# cpc_rct_mouse.net
KiCad netlist of a schematic drawn in EAGLE
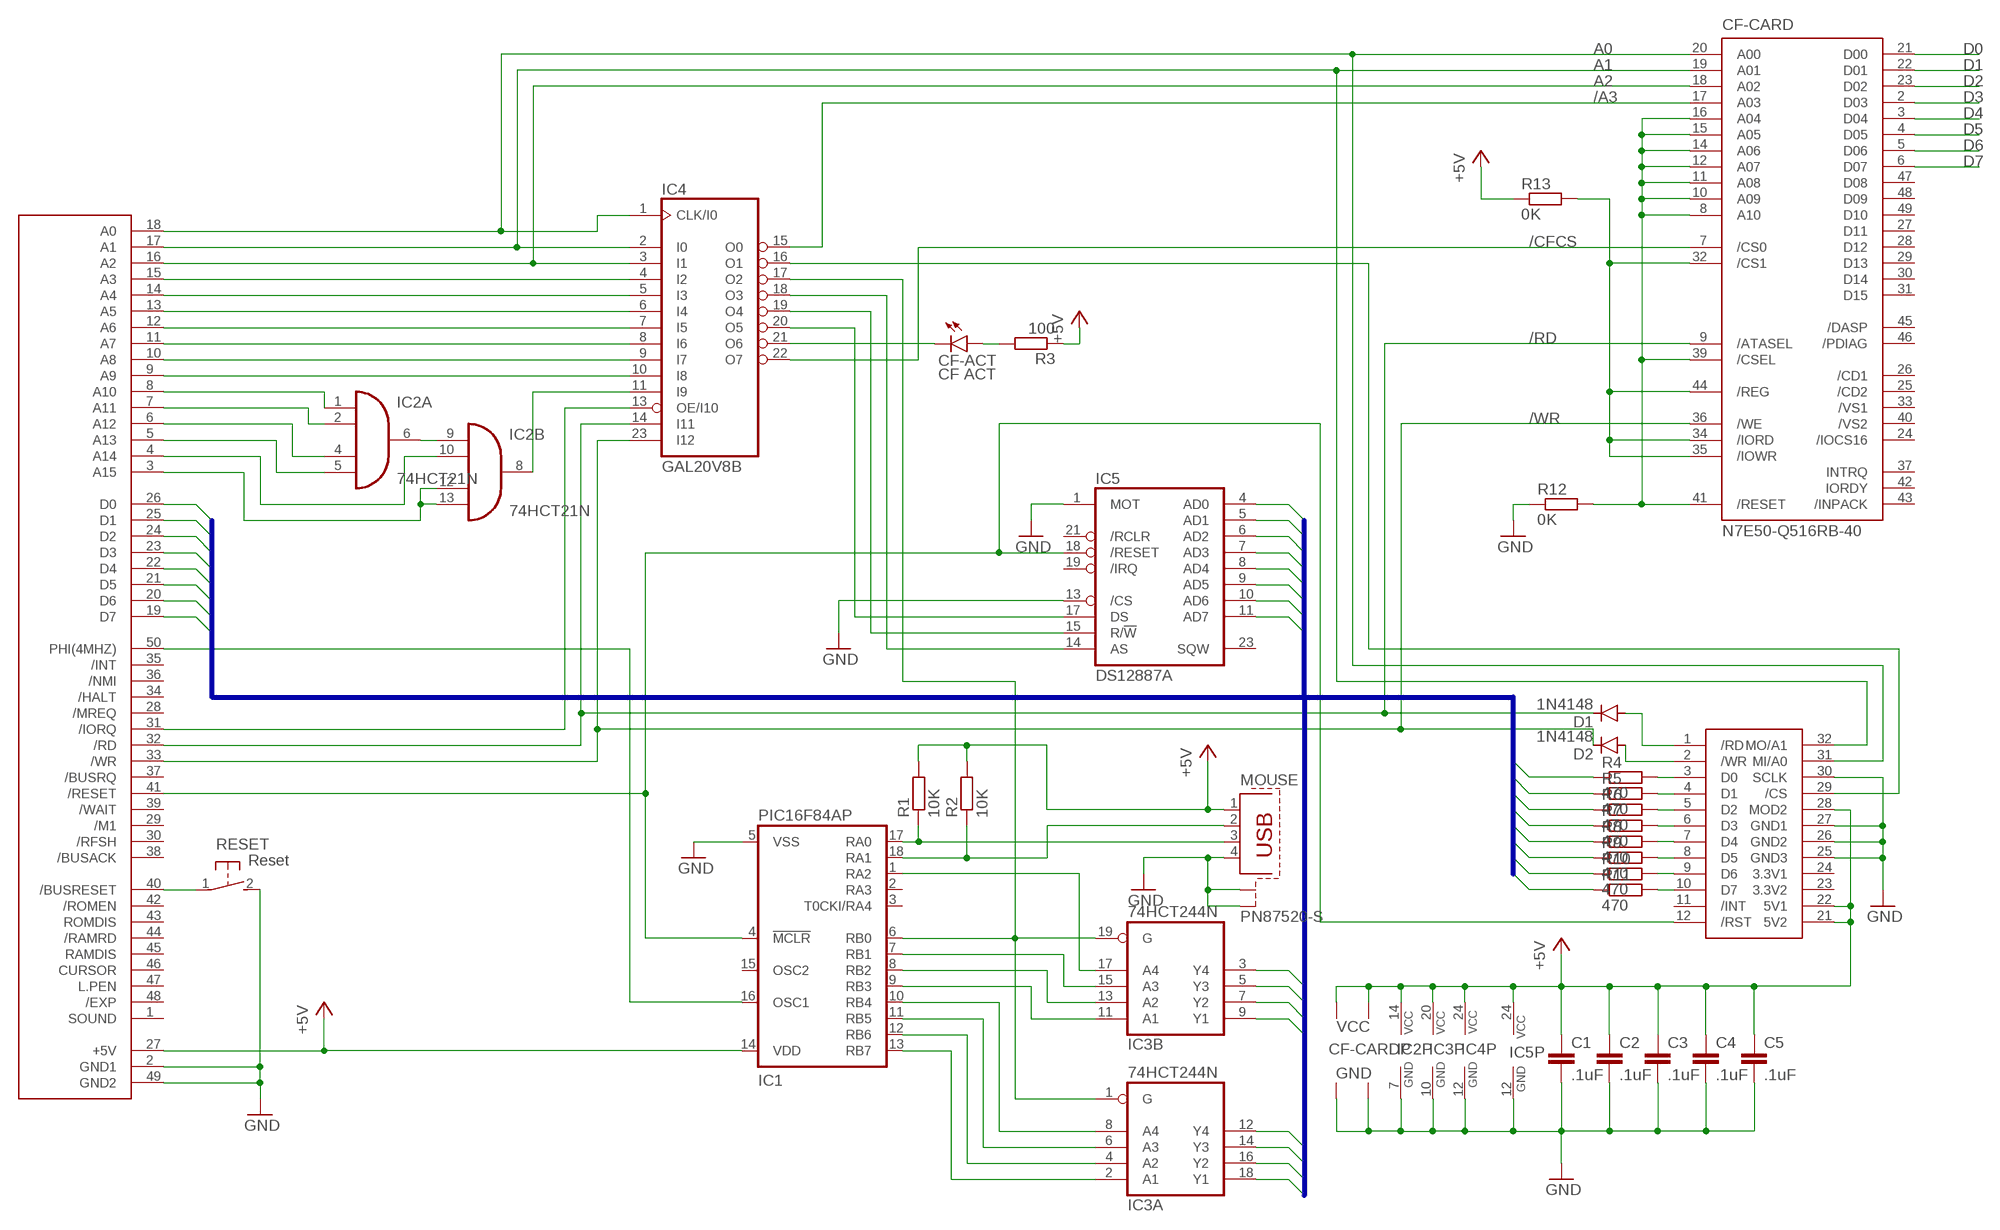
[diagram p0: schematic, sheet 1]

(export (version "E")
  (design (tool "Eeschema 10.0.6"))
  (components
    (comp (ref "C1")
      (value ".1uF")
      (footprint "eagle-import:C025-025X050")
      (libsource (lib "eagle-import") (part "C-EU025-025X050"))
    )
    (comp (ref "C2")
      (value ".1uF")
      (footprint "eagle-import:C025-025X050")
      (libsource (lib "eagle-import") (part "C-EU025-025X050"))
    )
    (comp (ref "C3")
      (value ".1uF")
      (footprint "eagle-import:C025-025X050")
      (libsource (lib "eagle-import") (part "C-EU025-025X050"))
    )
    (comp (ref "C4")
      (value ".1uF")
      (footprint "eagle-import:C025-025X050")
      (libsource (lib "eagle-import") (part "C-EU025-025X050"))
    )
    (comp (ref "C5")
      (value ".1uF")
      (footprint "eagle-import:C025-025X050")
      (libsource (lib "eagle-import") (part "C-EU025-025X050"))
    )
    (comp (ref "CF-ACT")
      (value "CF ACT")
      (footprint "eagle-import:LED3MM")
      (libsource (lib "eagle-import") (part "LED3MM"))
    )
    (comp (ref "CF-CARD")
      (value "N7E50-Q516RB-40")
      (footprint "eagle-import:3M-N7E50")
      (libsource (lib "eagle-import") (part "CF-CARD-HEADERHYBRID-1"))
    )
    (comp (ref "CON1")
      (value "CPCBUS")
      (footprint "eagle-import:2X25")
      (libsource (lib "eagle-import") (part "AMSTRAD_CPC_BUSP"))
    )
    (comp (ref "D1")
      (value "1N4148")
      (footprint "eagle-import:DO35-7")
      (libsource (lib "eagle-import") (part "1N4148DO35-7"))
    )
    (comp (ref "D2")
      (value "1N4148")
      (footprint "eagle-import:DO35-7")
      (libsource (lib "eagle-import") (part "1N4148DO35-7"))
    )
    (comp (ref "IC1")
      (value "PIC16F84AP")
      (footprint "eagle-import:DIL18")
      (fields (field (name "MF") "MICROCHIP") (field (name "MPN") "PIC16F84A-04I/P"))
      (libsource (lib "eagle-import") (part "PIC16F8P4A"))
    )
    (comp (ref "IC2")
      (value "74HCT21N")
      (footprint "eagle-import:DIL14")
      (libsource (lib "eagle-import") (part "7421NHC"))
    )
    (comp (ref "IC3")
      (value "74HCT244N")
      (footprint "eagle-import:DIL20")
      (libsource (lib "eagle-import") (part "74244NHCT"))
    )
    (comp (ref "IC4")
      (value "GAL20V8B")
      (footprint "eagle-import:DIL24-3")
      (fields (field (name "MF") "FARNELL") (field (name "MPN") "GAL20V8B-25QP"))
      (libsource (lib "eagle-import") (part "20V8"))
    )
    (comp (ref "IC5")
      (value "DS12887A")
      (footprint "eagle-import:DIL24")
      (libsource (lib "eagle-import") (part "DS12887"))
    )
    (comp (ref "MOUSE")
      (value "PN87520-S")
      (footprint "eagle-import:PN87520-S")
      (libsource (lib "eagle-import") (part "PN87520-S"))
    )
    (comp (ref "R1")
      (value "10K")
      (footprint "eagle-import:0204_7")
      (libsource (lib "eagle-import") (part "R-EU_0204/7"))
    )
    (comp (ref "R2")
      (value "10K")
      (footprint "eagle-import:0204_7")
      (libsource (lib "eagle-import") (part "R-EU_0204/7"))
    )
    (comp (ref "R3")
      (value "100")
      (footprint "eagle-import:0204_7")
      (libsource (lib "eagle-import") (part "R-EU_0204/7"))
    )
    (comp (ref "R4")
      (value "470")
      (footprint "eagle-import:0204_7")
      (libsource (lib "eagle-import") (part "R-EU_0204/7"))
    )
    (comp (ref "R5")
      (value "470")
      (footprint "eagle-import:0204_7")
      (libsource (lib "eagle-import") (part "R-EU_0204/7"))
    )
    (comp (ref "R6")
      (value "470")
      (footprint "eagle-import:0204_7")
      (libsource (lib "eagle-import") (part "R-EU_0204/7"))
    )
    (comp (ref "R7")
      (value "470")
      (footprint "eagle-import:0204_7")
      (libsource (lib "eagle-import") (part "R-EU_0204/7"))
    )
    (comp (ref "R8")
      (value "470")
      (footprint "eagle-import:0204_7")
      (libsource (lib "eagle-import") (part "R-EU_0204/7"))
    )
    (comp (ref "R9")
      (value "470")
      (footprint "eagle-import:0204_7")
      (libsource (lib "eagle-import") (part "R-EU_0204/7"))
    )
    (comp (ref "R10")
      (value "470")
      (footprint "eagle-import:0204_7")
      (libsource (lib "eagle-import") (part "R-EU_0204/7"))
    )
    (comp (ref "R11")
      (value "470")
      (footprint "eagle-import:0204_7")
      (libsource (lib "eagle-import") (part "R-EU_0204/7"))
    )
    (comp (ref "R12")
      (value "0K")
      (footprint "eagle-import:0204_7")
      (libsource (lib "eagle-import") (part "R-EU_0204/7"))
    )
    (comp (ref "R13")
      (value "0K")
      (footprint "eagle-import:0204_7")
      (libsource (lib "eagle-import") (part "R-EU_0204/7"))
    )
    (comp (ref "RESET")
      (value "Reset")
      (footprint "eagle-import:B3F-31XX")
      (fields (field (name "MPN") "B3F-3100"))
      (libsource (lib "eagle-import") (part "31-XX"))
    )
    (comp (ref "W5100S-MODULE")
      (value "W5100S-NETWORK-MODULE")
      (footprint "eagle-import:W5100S-NETWORK-MODULE")
      (libsource (lib "eagle-import") (part "W5100S-NETWORK-MODULE"))
    )
  )
  (nets
    (net (code "1") (name "+5V") (class "Default")
      (node (ref "C1") (pin "1") (pinfunction "1_1") (pintype "passive"))
      (node (ref "C2") (pin "1") (pinfunction "1_1") (pintype "passive"))
      (node (ref "C3") (pin "1") (pinfunction "1_1") (pintype "passive"))
      (node (ref "C4") (pin "1") (pinfunction "1_1") (pintype "passive"))
      (node (ref "C5") (pin "1") (pinfunction "1_1") (pintype "passive"))
      (node (ref "CF-CARD") (pin "13") (pinfunction "VCC2_13") (pintype "power_in"))
      (node (ref "CF-CARD") (pin "38") (pinfunction "VCC1_38") (pintype "power_in"))
      (node (ref "CON1") (pin "27") (pinfunction "+5V_27") (pintype "bidirectional"))
      (node (ref "IC1") (pin "14") (pinfunction "VDD_14") (pintype "power_in"))
      (node (ref "IC2") (pin "14") (pinfunction "VCC_14") (pintype "power_in"))
      (node (ref "IC3") (pin "20") (pinfunction "VCC_20") (pintype "power_in"))
      (node (ref "IC4") (pin "24") (pinfunction "VCC_24") (pintype "power_in"))
      (node (ref "IC5") (pin "24") (pinfunction "VCC_24") (pintype "power_in"))
      (node (ref "MOUSE") (pin "1") (pinfunction "1_1") (pintype "passive"))
      (node (ref "R1") (pin "2") (pinfunction "2_2") (pintype "passive"))
      (node (ref "R13") (pin "1") (pinfunction "1_1") (pintype "passive"))
      (node (ref "R2") (pin "2") (pinfunction "2_2") (pintype "passive"))
      (node (ref "R3") (pin "1") (pinfunction "1_1") (pintype "passive"))
      (node (ref "W5100S-MODULE") (pin "21") (pinfunction "5V2_21") (pintype "power_in"))
      (node (ref "W5100S-MODULE") (pin "22") (pinfunction "5V1_22") (pintype "power_in"))
      (node (ref "W5100S-MODULE") (pin "28") (pinfunction "MOD2_28") (pintype "passive"))
    )
    (net (code "2") (name "/3.3V1") (class "Default")
      (node (ref "W5100S-MODULE") (pin "24") (pinfunction "3.3V1_24") (pintype "power_in"))
    )
    (net (code "3") (name "/3.3V2") (class "Default")
      (node (ref "W5100S-MODULE") (pin "23") (pinfunction "3.3V2_23") (pintype "power_in"))
    )
    (net (code "4") (name "/A0") (class "Default")
      (node (ref "CF-CARD") (pin "20") (pinfunction "A00_20") (pintype "input"))
      (node (ref "CON1") (pin "18") (pinfunction "A0_18") (pintype "bidirectional"))
      (node (ref "IC4") (pin "1") (pinfunction "CLK/I0_1") (pintype "input"))
      (node (ref "W5100S-MODULE") (pin "31") (pinfunction "MI/A0_31") (pintype "input"))
    )
    (net (code "5") (name "/A1") (class "Default")
      (node (ref "CF-CARD") (pin "19") (pinfunction "A01_19") (pintype "input"))
      (node (ref "CON1") (pin "17") (pinfunction "A1_17") (pintype "bidirectional"))
      (node (ref "IC4") (pin "2") (pinfunction "I0_2") (pintype "input"))
      (node (ref "W5100S-MODULE") (pin "32") (pinfunction "MO/A1_32") (pintype "bidirectional"))
    )
    (net (code "6") (name "/A2") (class "Default")
      (node (ref "CF-CARD") (pin "18") (pinfunction "A02_18") (pintype "input"))
      (node (ref "CON1") (pin "16") (pinfunction "A2_16") (pintype "bidirectional"))
      (node (ref "IC4") (pin "3") (pinfunction "I1_3") (pintype "input"))
    )
    (net (code "7") (name "/D0") (class "Default")
      (node (ref "CF-CARD") (pin "21") (pinfunction "D00_21") (pintype "bidirectional"))
      (node (ref "CON1") (pin "26") (pinfunction "D0_26") (pintype "bidirectional"))
      (node (ref "IC3") (pin "3") (pinfunction "Y4_3") (pintype "tri_state"))
      (node (ref "IC5") (pin "4") (pinfunction "AD0_4") (pintype "bidirectional"))
      (node (ref "R4") (pin "1") (pinfunction "1_1") (pintype "passive"))
    )
    (net (code "8") (name "/D1") (class "Default")
      (node (ref "CF-CARD") (pin "22") (pinfunction "D01_22") (pintype "bidirectional"))
      (node (ref "CON1") (pin "25") (pinfunction "D1_25") (pintype "bidirectional"))
      (node (ref "IC3") (pin "5") (pinfunction "Y3_5") (pintype "tri_state"))
      (node (ref "IC5") (pin "5") (pinfunction "AD1_5") (pintype "bidirectional"))
      (node (ref "R5") (pin "1") (pinfunction "1_1") (pintype "passive"))
    )
    (net (code "9") (name "/D2") (class "Default")
      (node (ref "CF-CARD") (pin "23") (pinfunction "D02_23") (pintype "bidirectional"))
      (node (ref "CON1") (pin "24") (pinfunction "D2_24") (pintype "bidirectional"))
      (node (ref "IC3") (pin "7") (pinfunction "Y2_7") (pintype "tri_state"))
      (node (ref "IC5") (pin "6") (pinfunction "AD2_6") (pintype "bidirectional"))
      (node (ref "R6") (pin "1") (pinfunction "1_1") (pintype "passive"))
    )
    (net (code "10") (name "/D3") (class "Default")
      (node (ref "CF-CARD") (pin "2") (pinfunction "D03_2") (pintype "bidirectional"))
      (node (ref "CON1") (pin "23") (pinfunction "D3_23") (pintype "bidirectional"))
      (node (ref "IC3") (pin "9") (pinfunction "Y1_9") (pintype "tri_state"))
      (node (ref "IC5") (pin "7") (pinfunction "AD3_7") (pintype "bidirectional"))
      (node (ref "R7") (pin "1") (pinfunction "1_1") (pintype "passive"))
    )
    (net (code "11") (name "/D4") (class "Default")
      (node (ref "CF-CARD") (pin "3") (pinfunction "D04_3") (pintype "bidirectional"))
      (node (ref "CON1") (pin "22") (pinfunction "D4_22") (pintype "bidirectional"))
      (node (ref "IC3") (pin "12") (pinfunction "Y4_12") (pintype "tri_state"))
      (node (ref "IC5") (pin "8") (pinfunction "AD4_8") (pintype "bidirectional"))
      (node (ref "R8") (pin "1") (pinfunction "1_1") (pintype "passive"))
    )
    (net (code "12") (name "/D5") (class "Default")
      (node (ref "CF-CARD") (pin "4") (pinfunction "D05_4") (pintype "bidirectional"))
      (node (ref "CON1") (pin "21") (pinfunction "D5_21") (pintype "bidirectional"))
      (node (ref "IC3") (pin "14") (pinfunction "Y3_14") (pintype "tri_state"))
      (node (ref "IC5") (pin "9") (pinfunction "AD5_9") (pintype "bidirectional"))
      (node (ref "R9") (pin "1") (pinfunction "1_1") (pintype "passive"))
    )
    (net (code "13") (name "/D6") (class "Default")
      (node (ref "CF-CARD") (pin "5") (pinfunction "D06_5") (pintype "bidirectional"))
      (node (ref "CON1") (pin "20") (pinfunction "D6_20") (pintype "bidirectional"))
      (node (ref "IC3") (pin "16") (pinfunction "Y2_16") (pintype "tri_state"))
      (node (ref "IC5") (pin "10") (pinfunction "AD6_10") (pintype "bidirectional"))
      (node (ref "R10") (pin "1") (pinfunction "1_1") (pintype "passive"))
    )
    (net (code "14") (name "/D7") (class "Default")
      (node (ref "CF-CARD") (pin "6") (pinfunction "D07_6") (pintype "bidirectional"))
      (node (ref "CON1") (pin "19") (pinfunction "D7_19") (pintype "bidirectional"))
      (node (ref "IC3") (pin "18") (pinfunction "Y1_18") (pintype "tri_state"))
      (node (ref "IC5") (pin "11") (pinfunction "AD7_11") (pintype "bidirectional"))
      (node (ref "R11") (pin "1") (pinfunction "1_1") (pintype "passive"))
    )
    (net (code "15") (name "/{slash}A3") (class "Default")
      (node (ref "CF-CARD") (pin "17") (pinfunction "A03_17") (pintype "input"))
      (node (ref "IC4") (pin "15") (pinfunction "O0_15") (pintype "bidirectional"))
    )
    (net (code "16") (name "/{slash}CFCS") (class "Default")
      (node (ref "CF-CARD") (pin "7") (pinfunction "/CS0_7") (pintype "input"))
      (node (ref "IC4") (pin "22") (pinfunction "O7_22") (pintype "bidirectional"))
    )
    (net (code "17") (name "/{slash}RD") (class "Default")
      (node (ref "CF-CARD") (pin "9") (pinfunction "/ATASEL_9") (pintype "input"))
      (node (ref "CON1") (pin "32") (pinfunction "/RD_32") (pintype "bidirectional"))
      (node (ref "D1") (pin "C") (pinfunction "C_C") (pintype "passive"))
      (node (ref "IC4") (pin "14") (pinfunction "I11_14") (pintype "input"))
    )
    (net (code "18") (name "/{slash}WR") (class "Default")
      (node (ref "CF-CARD") (pin "36") (pinfunction "/WE_36") (pintype "input"))
      (node (ref "CON1") (pin "33") (pinfunction "/WR_33") (pintype "bidirectional"))
      (node (ref "D2") (pin "C") (pinfunction "C_C") (pintype "passive"))
      (node (ref "IC4") (pin "23") (pinfunction "I12_23") (pintype "input"))
    )
    (net (code "19") (name "GND") (class "Default")
      (node (ref "C1") (pin "2") (pinfunction "2_2") (pintype "passive"))
      (node (ref "C2") (pin "2") (pinfunction "2_2") (pintype "passive"))
      (node (ref "C3") (pin "2") (pinfunction "2_2") (pintype "passive"))
      (node (ref "C4") (pin "2") (pinfunction "2_2") (pintype "passive"))
      (node (ref "C5") (pin "2") (pinfunction "2_2") (pintype "passive"))
      (node (ref "CF-CARD") (pin "1") (pinfunction "GND1_1") (pintype "power_in"))
      (node (ref "CF-CARD") (pin "50") (pinfunction "GND2_50") (pintype "power_in"))
      (node (ref "CON1") (pin "2") (pinfunction "GND1_2") (pintype "bidirectional"))
      (node (ref "CON1") (pin "49") (pinfunction "GND2_49") (pintype "bidirectional"))
      (node (ref "IC1") (pin "5") (pinfunction "VSS_5") (pintype "power_in"))
      (node (ref "IC2") (pin "7") (pinfunction "GND_7") (pintype "power_in"))
      (node (ref "IC3") (pin "10") (pinfunction "GND_10") (pintype "power_in"))
      (node (ref "IC4") (pin "12") (pinfunction "GND_12") (pintype "power_in"))
      (node (ref "IC5") (pin "1") (pinfunction "MOT_1") (pintype "input"))
      (node (ref "IC5") (pin "12") (pinfunction "GND_12") (pintype "power_in"))
      (node (ref "IC5") (pin "13") (pinfunction "/CS_13") (pintype "input"))
      (node (ref "MOUSE") (pin "4") (pinfunction "4_4") (pintype "passive"))
      (node (ref "MOUSE") (pin "S1") (pinfunction "S1_S1") (pintype "passive"))
      (node (ref "MOUSE") (pin "S2") (pinfunction "S2_S2") (pintype "passive"))
      (node (ref "R12") (pin "1") (pinfunction "1_1") (pintype "passive"))
      (node (ref "RESET") (pin "2") (pinfunction "S_2") (pintype "passive"))
      (node (ref "W5100S-MODULE") (pin "25") (pinfunction "GND3_25") (pintype "power_in"))
      (node (ref "W5100S-MODULE") (pin "26") (pinfunction "GND2_26") (pintype "power_in"))
      (node (ref "W5100S-MODULE") (pin "27") (pinfunction "GND1_27") (pintype "power_in"))
      (node (ref "W5100S-MODULE") (pin "30") (pinfunction "SCLK_30") (pintype "output"))
    )
    (net (code "20") (name "Net-(CF-ACT-C)") (class "Default")
      (node (ref "CF-ACT") (pin "K") (pinfunction "C_K") (pintype "passive"))
      (node (ref "IC4") (pin "21") (pinfunction "O6_21") (pintype "bidirectional"))
    )
    (net (code "21") (name "Net-(CF-ACT-PadA)") (class "Default")
      (node (ref "CF-ACT") (pin "A") (pinfunction "A_A") (pintype "passive"))
      (node (ref "R3") (pin "2") (pinfunction "2_2") (pintype "passive"))
    )
    (net (code "22") (name "Net-(CF-CARDA-A04)") (class "Default")
      (node (ref "CF-CARD") (pin "10") (pinfunction "A09_10") (pintype "input"))
      (node (ref "CF-CARD") (pin "11") (pinfunction "A08_11") (pintype "input"))
      (node (ref "CF-CARD") (pin "12") (pinfunction "A07_12") (pintype "input"))
      (node (ref "CF-CARD") (pin "14") (pinfunction "A06_14") (pintype "input"))
      (node (ref "CF-CARD") (pin "15") (pinfunction "A05_15") (pintype "input"))
      (node (ref "CF-CARD") (pin "16") (pinfunction "A04_16") (pintype "input"))
      (node (ref "CF-CARD") (pin "39") (pinfunction "/CSEL_39") (pintype "input"))
      (node (ref "CF-CARD") (pin "41") (pinfunction "/RESET_41") (pintype "input"))
      (node (ref "CF-CARD") (pin "8") (pinfunction "A10_8") (pintype "input"))
      (node (ref "R12") (pin "2") (pinfunction "2_2") (pintype "passive"))
    )
    (net (code "23") (name "Net-(CF-CARDA-{slash}CS1)") (class "Default")
      (node (ref "CF-CARD") (pin "32") (pinfunction "/CS1_32") (pintype "input"))
      (node (ref "CF-CARD") (pin "34") (pinfunction "/IORD_34") (pintype "input"))
      (node (ref "CF-CARD") (pin "35") (pinfunction "/IOWR_35") (pintype "input"))
      (node (ref "CF-CARD") (pin "44") (pinfunction "/REG_44") (pintype "input"))
      (node (ref "R13") (pin "2") (pinfunction "2_2") (pintype "passive"))
    )
    (net (code "24") (name "Net-(CON1-A3)") (class "Default")
      (node (ref "CON1") (pin "15") (pinfunction "A3_15") (pintype "bidirectional"))
      (node (ref "IC4") (pin "4") (pinfunction "I2_4") (pintype "input"))
    )
    (net (code "25") (name "Net-(CON1-A4)") (class "Default")
      (node (ref "CON1") (pin "14") (pinfunction "A4_14") (pintype "bidirectional"))
      (node (ref "IC4") (pin "5") (pinfunction "I3_5") (pintype "input"))
    )
    (net (code "26") (name "Net-(CON1-A5)") (class "Default")
      (node (ref "CON1") (pin "13") (pinfunction "A5_13") (pintype "bidirectional"))
      (node (ref "IC4") (pin "6") (pinfunction "I4_6") (pintype "input"))
    )
    (net (code "27") (name "Net-(CON1-A6)") (class "Default")
      (node (ref "CON1") (pin "12") (pinfunction "A6_12") (pintype "bidirectional"))
      (node (ref "IC4") (pin "7") (pinfunction "I5_7") (pintype "input"))
    )
    (net (code "28") (name "Net-(CON1-A7)") (class "Default")
      (node (ref "CON1") (pin "11") (pinfunction "A7_11") (pintype "bidirectional"))
      (node (ref "IC4") (pin "8") (pinfunction "I6_8") (pintype "input"))
    )
    (net (code "29") (name "Net-(CON1-A8)") (class "Default")
      (node (ref "CON1") (pin "10") (pinfunction "A8_10") (pintype "bidirectional"))
      (node (ref "IC4") (pin "9") (pinfunction "I7_9") (pintype "input"))
    )
    (net (code "30") (name "Net-(CON1-A9)") (class "Default")
      (node (ref "CON1") (pin "9") (pinfunction "A9_9") (pintype "bidirectional"))
      (node (ref "IC4") (pin "10") (pinfunction "I8_10") (pintype "input"))
    )
    (net (code "31") (name "Net-(CON1-A10)") (class "Default")
      (node (ref "CON1") (pin "8") (pinfunction "A10_8") (pintype "bidirectional"))
      (node (ref "IC2") (pin "1") (pinfunction "I0_1") (pintype "input"))
    )
    (net (code "32") (name "Net-(CON1-A11)") (class "Default")
      (node (ref "CON1") (pin "7") (pinfunction "A11_7") (pintype "bidirectional"))
      (node (ref "IC2") (pin "2") (pinfunction "I1_2") (pintype "input"))
    )
    (net (code "33") (name "Net-(CON1-A12)") (class "Default")
      (node (ref "CON1") (pin "6") (pinfunction "A12_6") (pintype "bidirectional"))
      (node (ref "IC2") (pin "4") (pinfunction "I2_4") (pintype "input"))
    )
    (net (code "34") (name "Net-(CON1-A13)") (class "Default")
      (node (ref "CON1") (pin "5") (pinfunction "A13_5") (pintype "bidirectional"))
      (node (ref "IC2") (pin "5") (pinfunction "I3_5") (pintype "input"))
    )
    (net (code "35") (name "Net-(CON1-A14)") (class "Default")
      (node (ref "CON1") (pin "4") (pinfunction "A14_4") (pintype "bidirectional"))
      (node (ref "IC2") (pin "10") (pinfunction "I1_10") (pintype "input"))
    )
    (net (code "36") (name "Net-(CON1-A15)") (class "Default")
      (node (ref "CON1") (pin "3") (pinfunction "A15_3") (pintype "bidirectional"))
      (node (ref "IC2") (pin "12") (pinfunction "I2_12") (pintype "input"))
      (node (ref "IC2") (pin "13") (pinfunction "I3_13") (pintype "input"))
    )
    (net (code "37") (name "Net-(CON1-PHI(4MHZ))") (class "Default")
      (node (ref "CON1") (pin "50") (pinfunction "PHI(4MHZ)_50") (pintype "bidirectional"))
      (node (ref "IC1") (pin "16") (pinfunction "OSC1_16") (pintype "input"))
    )
    (net (code "38") (name "Net-(CON1-{slash}BUSRESET)") (class "Default")
      (node (ref "CON1") (pin "40") (pinfunction "/BUSRESET_40") (pintype "bidirectional"))
      (node (ref "RESET") (pin "1") (pinfunction "P_1") (pintype "passive"))
    )
    (net (code "39") (name "Net-(CON1-{slash}IORQ)") (class "Default")
      (node (ref "CON1") (pin "31") (pinfunction "/IORQ_31") (pintype "bidirectional"))
      (node (ref "IC4") (pin "13") (pinfunction "OE/I10_13") (pintype "input"))
    )
    (net (code "40") (name "Net-(CON1-{slash}RESET)") (class "Default")
      (node (ref "CON1") (pin "41") (pinfunction "/RESET_41") (pintype "bidirectional"))
      (node (ref "IC1") (pin "4") (pinfunction "~{MCLR}_4") (pintype "input"))
      (node (ref "IC5") (pin "18") (pinfunction "/RESET_18") (pintype "input"))
      (node (ref "W5100S-MODULE") (pin "12") (pinfunction "/RST_12") (pintype "input"))
    )
    (net (code "41") (name "Net-(IC1-RA0)") (class "Default")
      (node (ref "IC1") (pin "17") (pinfunction "RA0_17") (pintype "bidirectional"))
      (node (ref "MOUSE") (pin "3") (pinfunction "3_3") (pintype "passive"))
      (node (ref "R1") (pin "1") (pinfunction "1_1") (pintype "passive"))
    )
    (net (code "42") (name "Net-(IC1-RA1)") (class "Default")
      (node (ref "IC1") (pin "18") (pinfunction "RA1_18") (pintype "bidirectional"))
      (node (ref "MOUSE") (pin "2") (pinfunction "2_2") (pintype "passive"))
      (node (ref "R2") (pin "1") (pinfunction "1_1") (pintype "passive"))
    )
    (net (code "43") (name "Net-(IC1-RA2)") (class "Default")
      (node (ref "IC1") (pin "1") (pinfunction "RA2_1") (pintype "bidirectional"))
      (node (ref "IC3") (pin "17") (pinfunction "A4_17") (pintype "input"))
    )
    (net (code "44") (name "Net-(IC1-RB0)") (class "Default")
      (node (ref "IC1") (pin "6") (pinfunction "RB0_6") (pintype "bidirectional"))
      (node (ref "IC3") (pin "1") (pinfunction "G_1") (pintype "input"))
      (node (ref "IC3") (pin "19") (pinfunction "G_19") (pintype "input"))
      (node (ref "IC4") (pin "17") (pinfunction "O2_17") (pintype "bidirectional"))
    )
    (net (code "45") (name "Net-(IC1-RB1)") (class "Default")
      (node (ref "IC1") (pin "7") (pinfunction "RB1_7") (pintype "bidirectional"))
      (node (ref "IC3") (pin "15") (pinfunction "A3_15") (pintype "input"))
    )
    (net (code "46") (name "Net-(IC1-RB2)") (class "Default")
      (node (ref "IC1") (pin "8") (pinfunction "RB2_8") (pintype "bidirectional"))
      (node (ref "IC3") (pin "13") (pinfunction "A2_13") (pintype "input"))
    )
    (net (code "47") (name "Net-(IC1-RB3)") (class "Default")
      (node (ref "IC1") (pin "9") (pinfunction "RB3_9") (pintype "bidirectional"))
      (node (ref "IC3") (pin "11") (pinfunction "A1_11") (pintype "input"))
    )
    (net (code "48") (name "Net-(IC1-RB4)") (class "Default")
      (node (ref "IC1") (pin "10") (pinfunction "RB4_10") (pintype "bidirectional"))
      (node (ref "IC3") (pin "8") (pinfunction "A4_8") (pintype "input"))
    )
    (net (code "49") (name "Net-(IC1-RB5)") (class "Default")
      (node (ref "IC1") (pin "11") (pinfunction "RB5_11") (pintype "bidirectional"))
      (node (ref "IC3") (pin "6") (pinfunction "A3_6") (pintype "input"))
    )
    (net (code "50") (name "Net-(IC1-RB6)") (class "Default")
      (node (ref "IC1") (pin "12") (pinfunction "RB6_12") (pintype "bidirectional"))
      (node (ref "IC3") (pin "4") (pinfunction "A2_4") (pintype "input"))
    )
    (net (code "51") (name "Net-(IC1-RB7)") (class "Default")
      (node (ref "IC1") (pin "13") (pinfunction "RB7_13") (pintype "bidirectional"))
      (node (ref "IC3") (pin "2") (pinfunction "A1_2") (pintype "input"))
    )
    (net (code "52") (name "Net-(IC2A-O)") (class "Default")
      (node (ref "IC2") (pin "6") (pinfunction "O_6") (pintype "output"))
      (node (ref "IC2") (pin "9") (pinfunction "I0_9") (pintype "input"))
    )
    (net (code "53") (name "Net-(IC2B-O)") (class "Default")
      (node (ref "IC2") (pin "8") (pinfunction "O_8") (pintype "output"))
      (node (ref "IC4") (pin "11") (pinfunction "I9_11") (pintype "input"))
    )
    (net (code "54") (name "Net-(IC4A-O1)") (class "Default")
      (node (ref "IC4") (pin "16") (pinfunction "O1_16") (pintype "bidirectional"))
      (node (ref "W5100S-MODULE") (pin "29") (pinfunction "/CS_29") (pintype "input"))
    )
    (net (code "55") (name "Net-(IC4A-O3)") (class "Default")
      (node (ref "IC4") (pin "18") (pinfunction "O3_18") (pintype "bidirectional"))
      (node (ref "IC5") (pin "14") (pinfunction "AS_14") (pintype "input"))
    )
    (net (code "56") (name "Net-(IC4A-O4)") (class "Default")
      (node (ref "IC4") (pin "19") (pinfunction "O4_19") (pintype "bidirectional"))
      (node (ref "IC5") (pin "15") (pinfunction "R/~{W}_15") (pintype "input"))
    )
    (net (code "57") (name "Net-(IC4A-O5)") (class "Default")
      (node (ref "IC4") (pin "20") (pinfunction "O5_20") (pintype "bidirectional"))
      (node (ref "IC5") (pin "17") (pinfunction "DS_17") (pintype "input"))
    )
    (net (code "58") (name "Net-(W5100S-MODULE-D0)") (class "Default")
      (node (ref "R4") (pin "2") (pinfunction "2_2") (pintype "passive"))
      (node (ref "W5100S-MODULE") (pin "3") (pinfunction "D0_3") (pintype "bidirectional"))
    )
    (net (code "59") (name "Net-(W5100S-MODULE-D1)") (class "Default")
      (node (ref "R5") (pin "2") (pinfunction "2_2") (pintype "passive"))
      (node (ref "W5100S-MODULE") (pin "4") (pinfunction "D1_4") (pintype "bidirectional"))
    )
    (net (code "60") (name "Net-(W5100S-MODULE-D2)") (class "Default")
      (node (ref "R6") (pin "2") (pinfunction "2_2") (pintype "passive"))
      (node (ref "W5100S-MODULE") (pin "5") (pinfunction "D2_5") (pintype "bidirectional"))
    )
    (net (code "61") (name "Net-(W5100S-MODULE-D3)") (class "Default")
      (node (ref "R7") (pin "2") (pinfunction "2_2") (pintype "passive"))
      (node (ref "W5100S-MODULE") (pin "6") (pinfunction "D3_6") (pintype "bidirectional"))
    )
    (net (code "62") (name "Net-(W5100S-MODULE-D4)") (class "Default")
      (node (ref "R8") (pin "2") (pinfunction "2_2") (pintype "passive"))
      (node (ref "W5100S-MODULE") (pin "7") (pinfunction "D4_7") (pintype "bidirectional"))
    )
    (net (code "63") (name "Net-(W5100S-MODULE-D5)") (class "Default")
      (node (ref "R9") (pin "2") (pinfunction "2_2") (pintype "passive"))
      (node (ref "W5100S-MODULE") (pin "8") (pinfunction "D5_8") (pintype "bidirectional"))
    )
    (net (code "64") (name "Net-(W5100S-MODULE-D6)") (class "Default")
      (node (ref "R10") (pin "2") (pinfunction "2_2") (pintype "passive"))
      (node (ref "W5100S-MODULE") (pin "9") (pinfunction "D6_9") (pintype "bidirectional"))
    )
    (net (code "65") (name "Net-(W5100S-MODULE-D7)") (class "Default")
      (node (ref "R11") (pin "2") (pinfunction "2_2") (pintype "passive"))
      (node (ref "W5100S-MODULE") (pin "10") (pinfunction "D7_10") (pintype "bidirectional"))
    )
    (net (code "66") (name "Net-(W5100S-MODULE-{slash}RD)") (class "Default")
      (node (ref "D1") (pin "A") (pinfunction "A_A") (pintype "passive"))
      (node (ref "W5100S-MODULE") (pin "1") (pinfunction "/RD_1") (pintype "input"))
    )
    (net (code "67") (name "Net-(W5100S-MODULE-{slash}WR)") (class "Default")
      (node (ref "D2") (pin "A") (pinfunction "A_A") (pintype "passive"))
      (node (ref "W5100S-MODULE") (pin "2") (pinfunction "/WR_2") (pintype "input"))
    )
    (net (code "68") (name "unconnected-(CF-CARDA-D08-Pad47)") (class "Default")
      (node (ref "CF-CARD") (pin "47") (pinfunction "D08_47") (pintype "bidirectional"))
    )
    (net (code "69") (name "unconnected-(CF-CARDA-D09-Pad48)") (class "Default")
      (node (ref "CF-CARD") (pin "48") (pinfunction "D09_48") (pintype "bidirectional"))
    )
    (net (code "70") (name "unconnected-(CF-CARDA-D10-Pad49)") (class "Default")
      (node (ref "CF-CARD") (pin "49") (pinfunction "D10_49") (pintype "bidirectional"))
    )
    (net (code "71") (name "unconnected-(CF-CARDA-D11-Pad27)") (class "Default")
      (node (ref "CF-CARD") (pin "27") (pinfunction "D11_27") (pintype "bidirectional"))
    )
    (net (code "72") (name "unconnected-(CF-CARDA-D12-Pad28)") (class "Default")
      (node (ref "CF-CARD") (pin "28") (pinfunction "D12_28") (pintype "bidirectional"))
    )
    (net (code "73") (name "unconnected-(CF-CARDA-D13-Pad29)") (class "Default")
      (node (ref "CF-CARD") (pin "29") (pinfunction "D13_29") (pintype "bidirectional"))
    )
    (net (code "74") (name "unconnected-(CF-CARDA-D14-Pad30)") (class "Default")
      (node (ref "CF-CARD") (pin "30") (pinfunction "D14_30") (pintype "bidirectional"))
    )
    (net (code "75") (name "unconnected-(CF-CARDA-D15-Pad31)") (class "Default")
      (node (ref "CF-CARD") (pin "31") (pinfunction "D15_31") (pintype "bidirectional"))
    )
    (net (code "76") (name "unconnected-(CF-CARDA-INTRQ-Pad37)") (class "Default")
      (node (ref "CF-CARD") (pin "37") (pinfunction "INTRQ_37") (pintype "output"))
    )
    (net (code "77") (name "unconnected-(CF-CARDA-IORDY-Pad42)") (class "Default")
      (node (ref "CF-CARD") (pin "42") (pinfunction "IORDY_42") (pintype "output"))
    )
    (net (code "78") (name "unconnected-(CF-CARDA-{slash}CD1-Pad26)") (class "Default")
      (node (ref "CF-CARD") (pin "26") (pinfunction "/CD1_26") (pintype "output"))
    )
    (net (code "79") (name "unconnected-(CF-CARDA-{slash}CD2-Pad25)") (class "Default")
      (node (ref "CF-CARD") (pin "25") (pinfunction "/CD2_25") (pintype "output"))
    )
    (net (code "80") (name "unconnected-(CF-CARDA-{slash}DASP-Pad45)") (class "Default")
      (node (ref "CF-CARD") (pin "45") (pinfunction "/DASP_45") (pintype "bidirectional"))
    )
    (net (code "81") (name "unconnected-(CF-CARDA-{slash}INPACK-Pad43)") (class "Default")
      (node (ref "CF-CARD") (pin "43") (pinfunction "/INPACK_43") (pintype "output"))
    )
    (net (code "82") (name "unconnected-(CF-CARDA-{slash}IOCS16-Pad24)") (class "Default")
      (node (ref "CF-CARD") (pin "24") (pinfunction "/IOCS16_24") (pintype "output"))
    )
    (net (code "83") (name "unconnected-(CF-CARDA-{slash}PDIAG-Pad46)") (class "Default")
      (node (ref "CF-CARD") (pin "46") (pinfunction "/PDIAG_46") (pintype "bidirectional"))
    )
    (net (code "84") (name "unconnected-(CF-CARDA-{slash}VS1-Pad33)") (class "Default")
      (node (ref "CF-CARD") (pin "33") (pinfunction "/VS1_33") (pintype "output"))
    )
    (net (code "85") (name "unconnected-(CF-CARDA-{slash}VS2-Pad40)") (class "Default")
      (node (ref "CF-CARD") (pin "40") (pinfunction "/VS2_40") (pintype "output"))
    )
    (net (code "86") (name "unconnected-(CON1-CURSOR-Pad46)") (class "Default")
      (node (ref "CON1") (pin "46") (pinfunction "CURSOR_46") (pintype "bidirectional"))
    )
    (net (code "87") (name "unconnected-(CON1-L.PEN-Pad47)") (class "Default")
      (node (ref "CON1") (pin "47") (pinfunction "L.PEN_47") (pintype "bidirectional"))
    )
    (net (code "88") (name "unconnected-(CON1-RAMDIS-Pad45)") (class "Default")
      (node (ref "CON1") (pin "45") (pinfunction "RAMDIS_45") (pintype "bidirectional"))
    )
    (net (code "89") (name "unconnected-(CON1-ROMDIS-Pad43)") (class "Default")
      (node (ref "CON1") (pin "43") (pinfunction "ROMDIS_43") (pintype "bidirectional"))
    )
    (net (code "90") (name "unconnected-(CON1-SOUND-Pad1)") (class "Default")
      (node (ref "CON1") (pin "1") (pinfunction "SOUND_1") (pintype "bidirectional"))
    )
    (net (code "91") (name "unconnected-(CON1-{slash}BUSACK-Pad38)") (class "Default")
      (node (ref "CON1") (pin "38") (pinfunction "/BUSACK_38") (pintype "bidirectional"))
    )
    (net (code "92") (name "unconnected-(CON1-{slash}BUSRQ-Pad37)") (class "Default")
      (node (ref "CON1") (pin "37") (pinfunction "/BUSRQ_37") (pintype "bidirectional"))
    )
    (net (code "93") (name "unconnected-(CON1-{slash}EXP-Pad48)") (class "Default")
      (node (ref "CON1") (pin "48") (pinfunction "/EXP_48") (pintype "bidirectional"))
    )
    (net (code "94") (name "unconnected-(CON1-{slash}HALT-Pad34)") (class "Default")
      (node (ref "CON1") (pin "34") (pinfunction "/HALT_34") (pintype "bidirectional"))
    )
    (net (code "95") (name "unconnected-(CON1-{slash}INT-Pad35)") (class "Default")
      (node (ref "CON1") (pin "35") (pinfunction "/INT_35") (pintype "bidirectional"))
    )
    (net (code "96") (name "unconnected-(CON1-{slash}M1-Pad29)") (class "Default")
      (node (ref "CON1") (pin "29") (pinfunction "/M1_29") (pintype "bidirectional"))
    )
    (net (code "97") (name "unconnected-(CON1-{slash}MREQ-Pad28)") (class "Default")
      (node (ref "CON1") (pin "28") (pinfunction "/MREQ_28") (pintype "bidirectional"))
    )
    (net (code "98") (name "unconnected-(CON1-{slash}NMI-Pad36)") (class "Default")
      (node (ref "CON1") (pin "36") (pinfunction "/NMI_36") (pintype "bidirectional"))
    )
    (net (code "99") (name "unconnected-(CON1-{slash}RAMRD-Pad44)") (class "Default")
      (node (ref "CON1") (pin "44") (pinfunction "/RAMRD_44") (pintype "bidirectional"))
    )
    (net (code "100") (name "unconnected-(CON1-{slash}RFSH-Pad30)") (class "Default")
      (node (ref "CON1") (pin "30") (pinfunction "/RFSH_30") (pintype "bidirectional"))
    )
    (net (code "101") (name "unconnected-(CON1-{slash}ROMEN-Pad42)") (class "Default")
      (node (ref "CON1") (pin "42") (pinfunction "/ROMEN_42") (pintype "bidirectional"))
    )
    (net (code "102") (name "unconnected-(CON1-{slash}WAIT-Pad39)") (class "Default")
      (node (ref "CON1") (pin "39") (pinfunction "/WAIT_39") (pintype "bidirectional"))
    )
    (net (code "103") (name "unconnected-(IC1-OSC2-Pad15)") (class "Default")
      (node (ref "IC1") (pin "15") (pinfunction "OSC2_15") (pintype "output"))
    )
    (net (code "104") (name "unconnected-(IC1-RA3-Pad2)") (class "Default")
      (node (ref "IC1") (pin "2") (pinfunction "RA3_2") (pintype "bidirectional"))
    )
    (net (code "105") (name "unconnected-(IC1-T0CKI{slash}RA4-Pad3)") (class "Default")
      (node (ref "IC1") (pin "3") (pinfunction "T0CKI/RA4_3") (pintype "bidirectional"))
    )
    (net (code "106") (name "unconnected-(IC5A-SQW-Pad23)") (class "Default")
      (node (ref "IC5") (pin "23") (pinfunction "SQW_23") (pintype "output"))
    )
    (net (code "107") (name "unconnected-(IC5A-{slash}IRQ-Pad19)") (class "Default")
      (node (ref "IC5") (pin "19") (pinfunction "/IRQ_19") (pintype "output"))
    )
    (net (code "108") (name "unconnected-(IC5A-{slash}RCLR-Pad21)") (class "Default")
      (node (ref "IC5") (pin "21") (pinfunction "/RCLR_21") (pintype "input"))
    )
    (net (code "109") (name "unconnected-(W5100S-MODULE-{slash}INT-Pad11)") (class "Default")
      (node (ref "W5100S-MODULE") (pin "11") (pinfunction "/INT_11") (pintype "output"))
    )
  )
)
